# Schaltplan_Arm.net
KiCad netlist of a schematic drawn in EAGLE
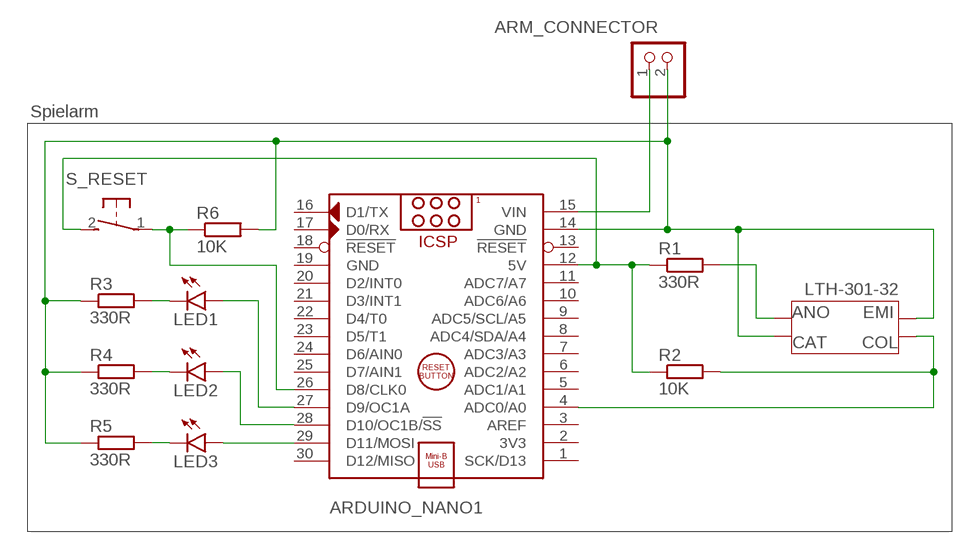
[diagram p0: schematic, sheet 1]

(export (version "E")
  (design (tool "Eeschema 10.0.6"))
  (components
    (comp (ref "ARDUINO_NANO1")
      (value "ARDUINO_NANO")
      (footprint "eagle-import:ARDUINO_NANO")
      (libsource (lib "eagle-import") (part "ARDUINO_NANO"))
    )
    (comp (ref "ARM_CONNECTOR")
      (value "PINHD-1X2")
      (footprint "eagle-import:1X02")
      (libsource (lib "eagle-import") (part "PINHD-1X2"))
    )
    (comp (ref "LED1")
      (value "LAP4-BOTTOM")
      (footprint "eagle-import:P47F-BOTTOM")
      (libsource (lib "eagle-import") (part "P4-BOTTOMLA"))
    )
    (comp (ref "LED2")
      (value "LAP4-BOTTOM")
      (footprint "eagle-import:P47F-BOTTOM")
      (libsource (lib "eagle-import") (part "P4-BOTTOMLA"))
    )
    (comp (ref "LED3")
      (value "LAP4-BOTTOM")
      (footprint "eagle-import:P47F-BOTTOM")
      (libsource (lib "eagle-import") (part "P4-BOTTOMLA"))
    )
    (comp (ref "R1")
      (value "330R")
      (footprint "eagle-import:0204V")
      (libsource (lib "eagle-import") (part "R-EU_0204/2V"))
    )
    (comp (ref "R2")
      (value "10K")
      (footprint "eagle-import:0204V")
      (libsource (lib "eagle-import") (part "R-EU_0204/2V"))
    )
    (comp (ref "R3")
      (value "330R")
      (footprint "eagle-import:0204V")
      (libsource (lib "eagle-import") (part "R-EU_0204/2V"))
    )
    (comp (ref "R4")
      (value "330R")
      (footprint "eagle-import:0204V")
      (libsource (lib "eagle-import") (part "R-EU_0204/2V"))
    )
    (comp (ref "R5")
      (value "330R")
      (footprint "eagle-import:0204V")
      (libsource (lib "eagle-import") (part "R-EU_0204/2V"))
    )
    (comp (ref "R6")
      (value "10K")
      (footprint "eagle-import:0204V")
      (libsource (lib "eagle-import") (part "R-EU_0204/2V"))
    )
    (comp (ref "S_RESET")
      (value "31-XX")
      (footprint "eagle-import:B3F-31XX")
      (fields (field (name "MPN") "B3F-3100"))
      (libsource (lib "eagle-import") (part "31-XX"))
    )
  )
  (nets
    (net (code "1") (name "/GND") (class "Default")
      (node (ref "ARDUINO_NANO1") (pin "19") (pinfunction "GND_19") (pintype "power_in"))
    )
    (net (code "2") (name "Net-(ARDUINO_NANO1-5V)") (class "Default")
      (node (ref "ARDUINO_NANO1") (pin "12") (pinfunction "5V_12") (pintype "power_in"))
      (node (ref "R1") (pin "1") (pinfunction "1_1") (pintype "passive"))
      (node (ref "R2") (pin "1") (pinfunction "1_1") (pintype "passive"))
      (node (ref "S_RESET") (pin "2") (pinfunction "S_2") (pintype "passive"))
    )
    (net (code "3") (name "Net-(ARDUINO_NANO1-ADC0{slash}A0)") (class "Default")
      (node (ref "ARDUINO_NANO1") (pin "4") (pinfunction "ADC0/A0_4") (pintype "bidirectional"))
      (node (ref "R2") (pin "2") (pinfunction "2_2") (pintype "passive"))
    )
    (net (code "4") (name "Net-(ARDUINO_NANO1-D8{slash}CLK0)") (class "Default")
      (node (ref "ARDUINO_NANO1") (pin "26") (pinfunction "D8/CLK0_26") (pintype "bidirectional"))
      (node (ref "R6") (pin "1") (pinfunction "1_1") (pintype "passive"))
      (node (ref "S_RESET") (pin "1") (pinfunction "P_1") (pintype "passive"))
    )
    (net (code "5") (name "Net-(ARDUINO_NANO1-D9{slash}OC1A)") (class "Default")
      (node (ref "ARDUINO_NANO1") (pin "27") (pinfunction "D9/OC1A_27") (pintype "bidirectional"))
      (node (ref "LED1") (pin "A") (pinfunction "A_A") (pintype "passive"))
    )
    (net (code "6") (name "Net-(ARDUINO_NANO1-D10{slash}OC1B{slash}~{SS})") (class "Default")
      (node (ref "ARDUINO_NANO1") (pin "28") (pinfunction "D10/OC1B/~{SS}_28") (pintype "bidirectional"))
      (node (ref "LED2") (pin "A") (pinfunction "A_A") (pintype "passive"))
    )
    (net (code "7") (name "Net-(ARDUINO_NANO1-D11{slash}MOSI)") (class "Default")
      (node (ref "ARDUINO_NANO1") (pin "29") (pinfunction "D11/MOSI_29") (pintype "bidirectional"))
      (node (ref "LED3") (pin "A") (pinfunction "A_A") (pintype "passive"))
    )
    (net (code "8") (name "Net-(ARDUINO_NANO1-GND-Pad14)") (class "Default")
      (node (ref "ARDUINO_NANO1") (pin "14") (pinfunction "GND_14") (pintype "power_in"))
      (node (ref "ARM_CONNECTOR") (pin "2") (pinfunction "2_2") (pintype "passive"))
      (node (ref "R3") (pin "1") (pinfunction "1_1") (pintype "passive"))
      (node (ref "R4") (pin "1") (pinfunction "1_1") (pintype "passive"))
      (node (ref "R5") (pin "1") (pinfunction "1_1") (pintype "passive"))
      (node (ref "R6") (pin "2") (pinfunction "2_2") (pintype "passive"))
    )
    (net (code "9") (name "Net-(ARDUINO_NANO1-VIN)") (class "Default")
      (node (ref "ARDUINO_NANO1") (pin "15") (pinfunction "VIN_15") (pintype "power_in"))
      (node (ref "ARM_CONNECTOR") (pin "1") (pinfunction "1_1") (pintype "passive"))
    )
    (net (code "10") (name "Net-(LED1-PadC)") (class "Default")
      (node (ref "LED1") (pin "C") (pinfunction "C_C") (pintype "passive"))
      (node (ref "R3") (pin "2") (pinfunction "2_2") (pintype "passive"))
    )
    (net (code "11") (name "Net-(LED2-PadC)") (class "Default")
      (node (ref "LED2") (pin "C") (pinfunction "C_C") (pintype "passive"))
      (node (ref "R4") (pin "2") (pinfunction "2_2") (pintype "passive"))
    )
    (net (code "12") (name "Net-(LED3-PadC)") (class "Default")
      (node (ref "LED3") (pin "C") (pinfunction "C_C") (pintype "passive"))
      (node (ref "R5") (pin "2") (pinfunction "2_2") (pintype "passive"))
    )
    (net (code "13") (name "unconnected-(ARDUINO_NANO1-3V3-Pad2)") (class "Default")
      (node (ref "ARDUINO_NANO1") (pin "2") (pinfunction "3V3_2") (pintype "output"))
    )
    (net (code "14") (name "unconnected-(ARDUINO_NANO1-ADC1{slash}A1-Pad5)") (class "Default")
      (node (ref "ARDUINO_NANO1") (pin "5") (pinfunction "ADC1/A1_5") (pintype "bidirectional"))
    )
    (net (code "15") (name "unconnected-(ARDUINO_NANO1-ADC2{slash}A2-Pad6)") (class "Default")
      (node (ref "ARDUINO_NANO1") (pin "6") (pinfunction "ADC2/A2_6") (pintype "bidirectional"))
    )
    (net (code "16") (name "unconnected-(ARDUINO_NANO1-ADC3{slash}A3-Pad7)") (class "Default")
      (node (ref "ARDUINO_NANO1") (pin "7") (pinfunction "ADC3/A3_7") (pintype "bidirectional"))
    )
    (net (code "17") (name "unconnected-(ARDUINO_NANO1-ADC4{slash}SDA{slash}A4-Pad8)") (class "Default")
      (node (ref "ARDUINO_NANO1") (pin "8") (pinfunction "ADC4/SDA/A4_8") (pintype "bidirectional"))
    )
    (net (code "18") (name "unconnected-(ARDUINO_NANO1-ADC5{slash}SCL{slash}A5-Pad9)") (class "Default")
      (node (ref "ARDUINO_NANO1") (pin "9") (pinfunction "ADC5/SCL/A5_9") (pintype "bidirectional"))
    )
    (net (code "19") (name "unconnected-(ARDUINO_NANO1-ADC6{slash}A6-Pad10)") (class "Default")
      (node (ref "ARDUINO_NANO1") (pin "10") (pinfunction "ADC6/A6_10") (pintype "bidirectional"))
    )
    (net (code "20") (name "unconnected-(ARDUINO_NANO1-ADC7{slash}A7-Pad11)") (class "Default")
      (node (ref "ARDUINO_NANO1") (pin "11") (pinfunction "ADC7/A7_11") (pintype "bidirectional"))
    )
    (net (code "21") (name "unconnected-(ARDUINO_NANO1-AREF-Pad3)") (class "Default")
      (node (ref "ARDUINO_NANO1") (pin "3") (pinfunction "AREF_3") (pintype "input"))
    )
    (net (code "22") (name "unconnected-(ARDUINO_NANO1-D0{slash}RX-Pad17)") (class "Default")
      (node (ref "ARDUINO_NANO1") (pin "17") (pinfunction "D0/RX_17") (pintype "bidirectional"))
    )
    (net (code "23") (name "unconnected-(ARDUINO_NANO1-D1{slash}TX-Pad16)") (class "Default")
      (node (ref "ARDUINO_NANO1") (pin "16") (pinfunction "D1/TX_16") (pintype "bidirectional"))
    )
    (net (code "24") (name "unconnected-(ARDUINO_NANO1-D2{slash}INT0-Pad20)") (class "Default")
      (node (ref "ARDUINO_NANO1") (pin "20") (pinfunction "D2/INT0_20") (pintype "bidirectional"))
    )
    (net (code "25") (name "unconnected-(ARDUINO_NANO1-D3{slash}INT1-Pad21)") (class "Default")
      (node (ref "ARDUINO_NANO1") (pin "21") (pinfunction "D3/INT1_21") (pintype "bidirectional"))
    )
    (net (code "26") (name "unconnected-(ARDUINO_NANO1-D4{slash}T0-Pad22)") (class "Default")
      (node (ref "ARDUINO_NANO1") (pin "22") (pinfunction "D4/T0_22") (pintype "bidirectional"))
    )
    (net (code "27") (name "unconnected-(ARDUINO_NANO1-D5{slash}T1-Pad23)") (class "Default")
      (node (ref "ARDUINO_NANO1") (pin "23") (pinfunction "D5/T1_23") (pintype "bidirectional"))
    )
    (net (code "28") (name "unconnected-(ARDUINO_NANO1-D6{slash}AIN0-Pad24)") (class "Default")
      (node (ref "ARDUINO_NANO1") (pin "24") (pinfunction "D6/AIN0_24") (pintype "bidirectional"))
    )
    (net (code "29") (name "unconnected-(ARDUINO_NANO1-D7{slash}AIN1-Pad25)") (class "Default")
      (node (ref "ARDUINO_NANO1") (pin "25") (pinfunction "D7/AIN1_25") (pintype "bidirectional"))
    )
    (net (code "30") (name "unconnected-(ARDUINO_NANO1-D12{slash}MISO-Pad30)") (class "Default")
      (node (ref "ARDUINO_NANO1") (pin "30") (pinfunction "D12/MISO_30") (pintype "bidirectional"))
    )
    (net (code "31") (name "unconnected-(ARDUINO_NANO1-SCK{slash}D13-Pad1)") (class "Default")
      (node (ref "ARDUINO_NANO1") (pin "1") (pinfunction "SCK/D13_1") (pintype "bidirectional"))
    )
    (net (code "32") (name "unconnected-(ARDUINO_NANO1-~{RESET}-Pad13)") (class "Default")
      (node (ref "ARDUINO_NANO1") (pin "13") (pinfunction "~{RESET}_13") (pintype "input"))
    )
    (net (code "33") (name "unconnected-(ARDUINO_NANO1-~{RESET}-Pad18)") (class "Default")
      (node (ref "ARDUINO_NANO1") (pin "18") (pinfunction "~{RESET}_18") (pintype "input"))
    )
    (net (code "34") (name "unconnected-(R1-Pad2)") (class "Default")
      (node (ref "R1") (pin "2") (pinfunction "2_2") (pintype "passive"))
    )
  )
)
